# USB-NSTr_v3.net
KiCad netlist of a schematic drawn in Altium Designer
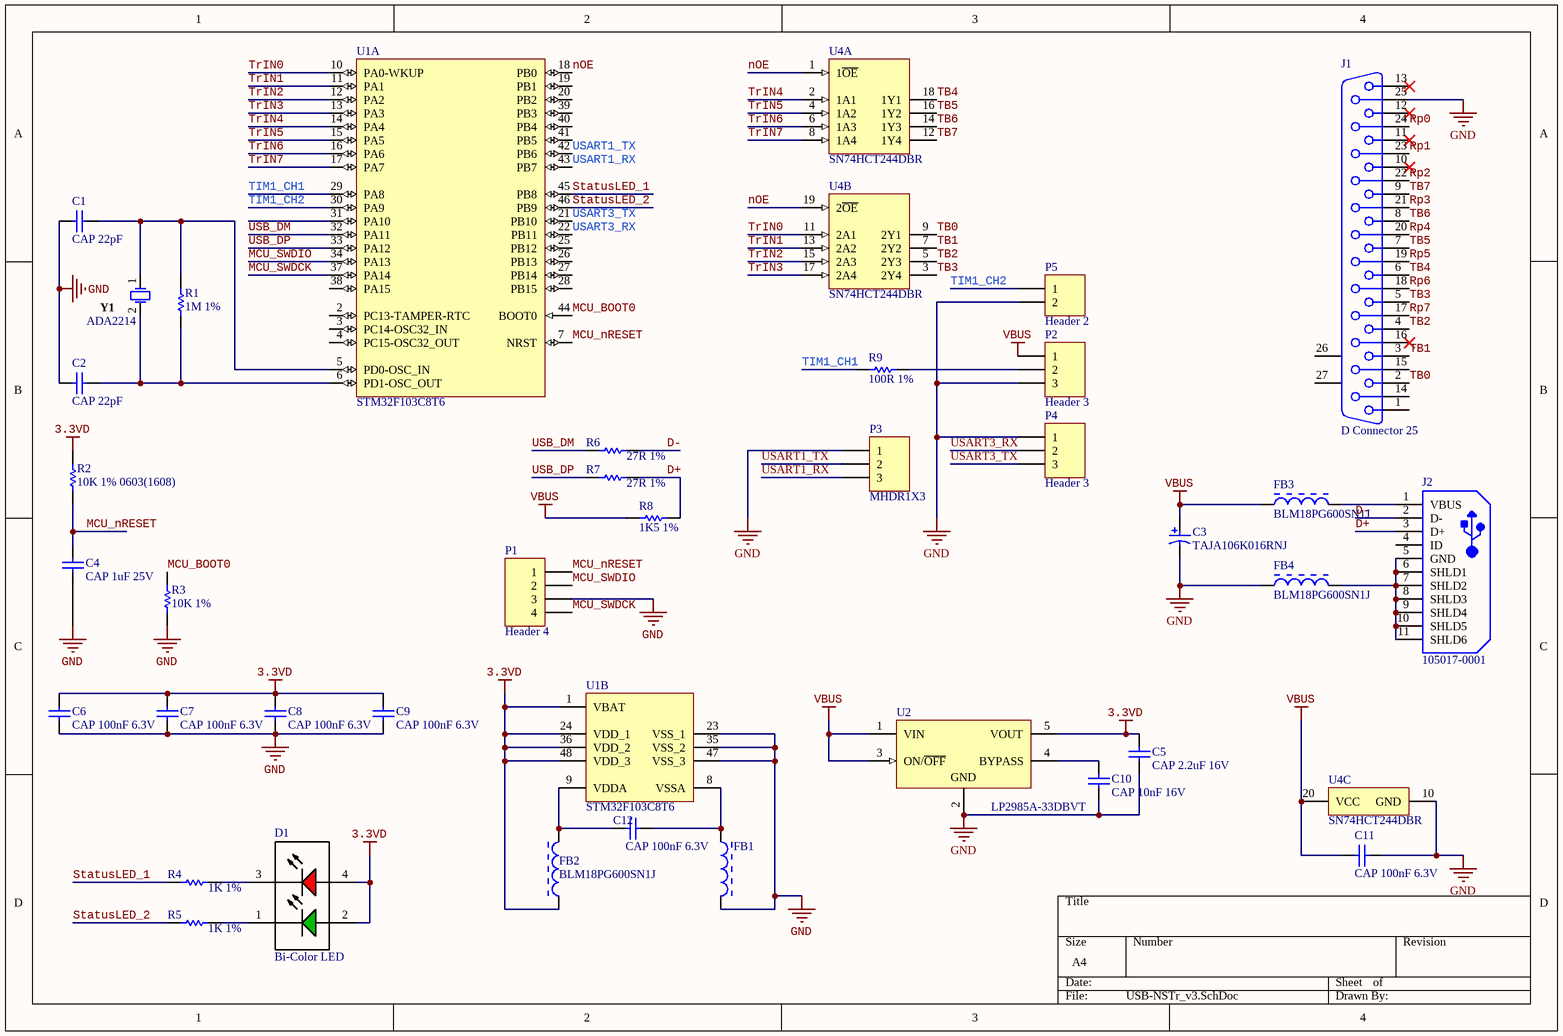
[diagram p0: USB-NSTr_v3.SchDoc]

(export (version "E")
  (design (tool "Eeschema 10.0.6"))
  (components
    (comp (ref "C1")
      (value "CAP 22pF")
      (footprint "CAPC0603(1608)100_N")
      (description "CAP 22pF 16V ±10% 0603 (1608 Metric) Thickness 1mm SMD")
      (fields (field (name "TOLERANCE") "Â±10%"))
      (libsource (lib "Altium Content Vault") (part "CAP"))
    )
    (comp (ref "C2")
      (value "CAP 22pF")
      (footprint "CAPC0603(1608)100_N")
      (description "CAP 22pF 16V ±10% 0603 (1608 Metric) Thickness 1mm SMD")
      (fields (field (name "TOLERANCE") "Â±10%"))
      (libsource (lib "Altium Content Vault") (part "CAP"))
    )
    (comp (ref "C3")
      (value "TAJA106K016RNJ")
      (footprint "CAPMP3217X18-T_V")
      (description "Standard Tantalum, 10 uF, +/- 10%, 16 V, -55 to 125 degC, 2-Pin SMD (1206), RoHS, Tape and Reel")
      (libsource (lib "Altium Content Vault") (part "CAP-P-2"))
    )
    (comp (ref "C4")
      (value "CAP 1uF 25V")
      (footprint "CAPC0603(1608)100_N")
      (description "CAP 1uF 25V ±20% 0603 (1608 Metric) Thickness 1mm SMD")
      (fields (field (name "TOLERANCE") "Â±20%"))
      (libsource (lib "Altium Content Vault") (part "CAP"))
    )
    (comp (ref "C5")
      (value "CAP 2.2uF 16V")
      (footprint "CAPC0603(1608)55_N")
      (description "CAP 2.2uF 16V ±20% 0603 (1608 Metric) Thickness 0.55mm SMD")
      (fields (field (name "TOLERANCE") "Â±20%"))
      (libsource (lib "Altium Content Vault") (part "CAP"))
    )
    (comp (ref "C6")
      (value "CAP 100nF 6.3V")
      (footprint "CAPC0603(1608)100_N")
      (description "CAP 100nF 6.3V ±10% 0603 (1608 Metric) Thickness 1mm SMD")
      (fields (field (name "TOLERANCE") "Â±10%"))
      (libsource (lib "Altium Content Vault") (part "CAP"))
    )
    (comp (ref "C7")
      (value "CAP 100nF 6.3V")
      (footprint "CAPC0603(1608)100_N")
      (description "CAP 100nF 6.3V ±10% 0603 (1608 Metric) Thickness 1mm SMD")
      (fields (field (name "TOLERANCE") "Â±10%"))
      (libsource (lib "Altium Content Vault") (part "CAP"))
    )
    (comp (ref "C8")
      (value "CAP 100nF 6.3V")
      (footprint "CAPC0603(1608)100_N")
      (description "CAP 100nF 6.3V ±10% 0603 (1608 Metric) Thickness 1mm SMD")
      (fields (field (name "TOLERANCE") "Â±10%"))
      (libsource (lib "Altium Content Vault") (part "CAP"))
    )
    (comp (ref "C9")
      (value "CAP 100nF 6.3V")
      (footprint "CAPC0603(1608)100_N")
      (description "CAP 100nF 6.3V ±10% 0603 (1608 Metric) Thickness 1mm SMD")
      (fields (field (name "TOLERANCE") "Â±10%"))
      (libsource (lib "Altium Content Vault") (part "CAP"))
    )
    (comp (ref "C10")
      (value "CAP 10nF 16V")
      (footprint "CAPC0603(1608)100_N")
      (description "CAP 10nF 16V ±5% 0603 (1608 Metric) Thickness 1mm SMD")
      (fields (field (name "TOLERANCE") "Â±5%"))
      (libsource (lib "Altium Content Vault") (part "CAP"))
    )
    (comp (ref "C11")
      (value "CAP 100nF 6.3V")
      (footprint "CAPC0603(1608)100_N")
      (description "CAP 100nF 6.3V ±10% 0603 (1608 Metric) Thickness 1mm SMD")
      (fields (field (name "TOLERANCE") "Â±10%"))
      (libsource (lib "Altium Content Vault") (part "CAP"))
    )
    (comp (ref "C12")
      (value "CAP 100nF 6.3V")
      (footprint "CAPC0603(1608)100_N")
      (description "CAP 100nF 6.3V ±10% 0603 (1608 Metric) Thickness 1mm SMD")
      (fields (field (name "TOLERANCE") "Â±10%"))
      (libsource (lib "Altium Content Vault") (part "CAP"))
    )
    (comp (ref "D1")
      (value "Bi-Color LED")
      (footprint "LED_Bi_Color_1204")
      (description "LED Indicator, Red / Green, 2 V, -40 to 100 degC, 4-Pin SMD, RoHS, Tape and Reel")
      (fields (field (name "MANUFACTURER") "Dialight"))
      (libsource (lib "MDR-36") (part "LED-RG-KAAK-4"))
    )
    (comp (ref "FB1")
      (value "BLM18PG600SN1J")
      (footprint "MURA-BLM18PG_KG-CHIP-2_V2")
      (fields (field (name "MANUFACTURER") "Murata"))
      (libsource (lib "Altium Content Vault") (part "MURA-FB-2"))
    )
    (comp (ref "FB2")
      (value "BLM18PG600SN1J")
      (footprint "MURA-BLM18PG_KG-CHIP-2_V2")
      (fields (field (name "MANUFACTURER") "Murata"))
      (libsource (lib "Altium Content Vault") (part "MURA-FB-2"))
    )
    (comp (ref "FB3")
      (value "BLM18PG600SN1J")
      (footprint "MURA-BLM18PG_KG-CHIP-2_V2")
      (fields (field (name "MANUFACTURER") "Murata"))
      (libsource (lib "Altium Content Vault") (part "MURA-FB-2"))
    )
    (comp (ref "FB4")
      (value "BLM18PG600SN1J")
      (footprint "MURA-BLM18PG_KG-CHIP-2_V2")
      (fields (field (name "MANUFACTURER") "Murata"))
      (libsource (lib "Altium Content Vault") (part "MURA-FB-2"))
    )
    (comp (ref "J1")
      (value "D Connector 25")
      (footprint "DB25-EDGE-Female-S")
      (description "Receptacle Assembly, 25 Position, Right Angle")
      (fields (field (name "PUBLISHER") "Altium Limited"))
      (libsource (lib "Miscellaneous Connectors") (part "D Connector 25"))
    )
    (comp (ref "J2")
      (value "105017-0001")
      (footprint "USB-MICRO-B_V")
      (fields (field (name "MANUFACTURER") "Molex"))
      (libsource (lib "Altium Content Vault") (part "USB-5-6SHLD"))
    )
    (comp (ref "P1")
      (value "Header 4")
      (footprint "PH2.0-LI-4P")
      (description "Header, 4-Pin")
      (fields (field (name "PUBLISHER") "Altium Limited"))
      (libsource (lib "Miscellaneous Connectors") (part "Header 4"))
    )
    (comp (ref "P2")
      (value "Header 3")
      (footprint "HDR1X3")
      (description "Header, 3-Pin")
      (fields (field (name "PUBLISHER") "Altium Limited"))
      (libsource (lib "Miscellaneous Connectors") (part "Header 3"))
    )
    (comp (ref "P3")
      (value "MHDR1X3")
      (footprint "HDR1X3")
      (description "Header, 3-Pin")
      (fields (field (name "PUBLISHER") "Altium Limited"))
      (libsource (lib "Miscellaneous Connectors") (part "MHDR1X3"))
    )
    (comp (ref "P4")
      (value "Header 3")
      (footprint "HDR1X3")
      (description "Header, 3-Pin")
      (fields (field (name "PUBLISHER") "Altium Limited"))
      (libsource (lib "Miscellaneous Connectors") (part "Header 3"))
    )
    (comp (ref "P5")
      (value "Header 2")
      (footprint "HDR1X2")
      (description "Header, 2-Pin")
      (fields (field (name "PUBLISHER") "Altium Limited"))
      (libsource (lib "Miscellaneous Connectors") (part "Header 2"))
    )
    (comp (ref "R1")
      (value "1M 1%")
      (footprint "RESC0603(1608)_N")
      (description "1M 0.1W 1% 0603 (1608 Metric)  SMD")
      (fields (field (name "POWER") "0.1 W") (field (name "TOLERANCE") "1 %"))
      (libsource (lib "Altium Content Vault") (part "RES"))
    )
    (comp (ref "R2")
      (value "10K 1% 0603(1608)")
      (footprint "RESC0603(1608)_N")
      (description "10K 0.1W 1% 0603 (1608 Metric)  SMD")
      (fields (field (name "POWER") "0.1 W") (field (name "TOLERANCE") "1 %"))
      (libsource (lib "Altium Content Vault") (part "RES"))
    )
    (comp (ref "R3")
      (value "10K 1%")
      (footprint "RESC0603(1608)_N")
      (description "10K 0.1W 1% 0603 (1608 Metric)  SMD")
      (fields (field (name "POWER") "0.1 W") (field (name "TOLERANCE") "1 %"))
      (libsource (lib "Altium Content Vault") (part "RES"))
    )
    (comp (ref "R4")
      (value "1K 1%")
      (footprint "RESC0603(1608)_N")
      (description "1K 0.1W 1% 0603 (1608 Metric)  SMD")
      (fields (field (name "TOLERANCE") "1 %") (field (name "POWER") "0.1 W"))
      (libsource (lib "Altium Content Vault") (part "RES"))
    )
    (comp (ref "R5")
      (value "1K 1%")
      (footprint "RESC0603(1608)_N")
      (description "1K 0.1W 1% 0603 (1608 Metric)  SMD")
      (fields (field (name "TOLERANCE") "1 %") (field (name "POWER") "0.1 W"))
      (libsource (lib "Altium Content Vault") (part "RES"))
    )
    (comp (ref "R6")
      (value "27R 1%")
      (footprint "RESC0603(1608)_N")
      (description "27R 0.1W 1% 0603 (1608 Metric)  SMD")
      (fields (field (name "TOLERANCE") "1 %") (field (name "POWER") "0.1 W"))
      (libsource (lib "Altium Content Vault") (part "RES"))
    )
    (comp (ref "R7")
      (value "27R 1%")
      (footprint "RESC0603(1608)_N")
      (description "27R 0.1W 1% 0603 (1608 Metric)  SMD")
      (fields (field (name "TOLERANCE") "1 %") (field (name "POWER") "0.1 W"))
      (libsource (lib "Altium Content Vault") (part "RES"))
    )
    (comp (ref "R8")
      (value "1K5 1%")
      (footprint "RESC0805(2012)_N")
      (description "1K5 0.125W 1% 0805 (2012 Metric)  SMD")
      (fields (field (name "POWER") "0.125 W") (field (name "TOLERANCE") "1 %"))
      (libsource (lib "Altium Content Vault") (part "RES"))
    )
    (comp (ref "R9")
      (value "100R 1%")
      (footprint "RESC0603(1608)_N")
      (description "100R 0.1W 1% 0603 (1608 Metric)  SMD")
      (fields (field (name "TOLERANCE") "1 %") (field (name "POWER") "0.1 W"))
      (libsource (lib "Altium Content Vault") (part "RES"))
    )
    (comp (ref "U1")
      (value "STM32F103C8T6")
      (footprint "STM-LQFP48_N")
      (libsource (lib "Altium Content Vault") (part "MC-ARM-STM32F103X8_B-SQ48"))
    )
    (comp (ref "U2")
      (value "LP2985A-33DBVT")
      (footprint "DBV0005A_N")
      (fields (field (name "MANUFACTURER") "Texas Instruments"))
      (libsource (lib "Altium Content Vault") (part "TI-LP2985_A-10DBV5"))
    )
    (comp (ref "U4")
      (value "SN74HCT244DBR")
      (footprint "DB0020A_N")
      (description "Octal Buffers And Line Drivers With 3-State Outputs, DB0020A, LARGE T&R")
      (fields
        (field (name "MANUFACTURER") "Texas Instruments")
        (field (name "GENERIC PART NUMBER") "SN74HCT244")
      )
      (libsource (lib "Altium Content Vault") (part "TI-SN54_74-XX020A-20"))
    )
    (comp (ref "Y1")
      (value "ADA2214")
      (footprint "ADAI-THHF-49S3")
      (description "Crystal, 12 MHz, 18 pF, 30 PPM, -20 to 70 degC, 2-Pin THD, RoHS")
      (libsource (lib "Altium Content Vault") (part "XTAL-1-2-2"))
    )
  )
  (nets
    (net (code "1") (name "/D+") (class "Default")
      (node (ref "J2") (pin "3") (pinfunction "D+_3") (pintype "passive"))
      (node (ref "R7") (pin "2") (pinfunction "2_2") (pintype "passive"))
      (node (ref "R8") (pin "1") (pinfunction "1_1") (pintype "passive"))
    )
    (net (code "2") (name "/D-") (class "Default")
      (node (ref "J2") (pin "2") (pinfunction "D-_2") (pintype "passive"))
      (node (ref "R6") (pin "2") (pinfunction "2_2") (pintype "passive"))
    )
    (net (code "3") (name "/MCU_BOOT0") (class "Default")
      (node (ref "R3") (pin "2") (pinfunction "2_2") (pintype "passive"))
      (node (ref "U1") (pin "44") (pinfunction "BOOT0_44") (pintype "input"))
    )
    (net (code "4") (name "/MCU_SWDCK") (class "Default")
      (node (ref "P1") (pin "4") (pinfunction "4_4") (pintype "passive"))
      (node (ref "U1") (pin "37") (pinfunction "PA14_37") (pintype "bidirectional"))
    )
    (net (code "5") (name "/MCU_SWDIO") (class "Default")
      (node (ref "P1") (pin "2") (pinfunction "2_2") (pintype "passive"))
      (node (ref "U1") (pin "34") (pinfunction "PA13_34") (pintype "bidirectional"))
    )
    (net (code "6") (name "/MCU_nRESET") (class "Default")
      (node (ref "C4") (pin "2") (pinfunction "2_2") (pintype "passive"))
      (node (ref "P1") (pin "1") (pinfunction "1_1") (pintype "passive"))
      (node (ref "R2") (pin "1") (pinfunction "1_1") (pintype "passive"))
      (node (ref "U1") (pin "7") (pinfunction "NRST_7") (pintype "bidirectional"))
    )
    (net (code "7") (name "/Rp0") (class "Default")
      (node (ref "J1") (pin "24") (pinfunction "24_24") (pintype "passive"))
    )
    (net (code "8") (name "/Rp1") (class "Default")
      (node (ref "J1") (pin "23") (pinfunction "23_23") (pintype "passive"))
    )
    (net (code "9") (name "/Rp2") (class "Default")
      (node (ref "J1") (pin "22") (pinfunction "22_22") (pintype "passive"))
    )
    (net (code "10") (name "/Rp3") (class "Default")
      (node (ref "J1") (pin "21") (pinfunction "21_21") (pintype "passive"))
    )
    (net (code "11") (name "/Rp4") (class "Default")
      (node (ref "J1") (pin "20") (pinfunction "20_20") (pintype "passive"))
    )
    (net (code "12") (name "/Rp5") (class "Default")
      (node (ref "J1") (pin "19") (pinfunction "19_19") (pintype "passive"))
    )
    (net (code "13") (name "/Rp6") (class "Default")
      (node (ref "J1") (pin "18") (pinfunction "18_18") (pintype "passive"))
    )
    (net (code "14") (name "/Rp7") (class "Default")
      (node (ref "J1") (pin "17") (pinfunction "17_17") (pintype "passive"))
    )
    (net (code "15") (name "/StatusLED_1") (class "Default")
      (node (ref "R4") (pin "1") (pinfunction "1_1") (pintype "passive"))
      (node (ref "U1") (pin "45") (pinfunction "PB8_45") (pintype "bidirectional"))
    )
    (net (code "16") (name "/StatusLED_2") (class "Default")
      (node (ref "R5") (pin "1") (pinfunction "1_1") (pintype "passive"))
      (node (ref "U1") (pin "46") (pinfunction "PB9_46") (pintype "bidirectional"))
    )
    (net (code "17") (name "/TB0") (class "Default")
      (node (ref "J1") (pin "2") (pinfunction "2_2") (pintype "passive"))
      (node (ref "U4") (pin "9") (pinfunction "2Y1_9") (pintype "tri_state"))
    )
    (net (code "18") (name "/TB1") (class "Default")
      (node (ref "J1") (pin "3") (pinfunction "3_3") (pintype "passive"))
      (node (ref "U4") (pin "7") (pinfunction "2Y2_7") (pintype "tri_state"))
    )
    (net (code "19") (name "/TB2") (class "Default")
      (node (ref "J1") (pin "4") (pinfunction "4_4") (pintype "passive"))
      (node (ref "U4") (pin "5") (pinfunction "2Y3_5") (pintype "tri_state"))
    )
    (net (code "20") (name "/TB3") (class "Default")
      (node (ref "J1") (pin "5") (pinfunction "5_5") (pintype "passive"))
      (node (ref "U4") (pin "3") (pinfunction "2Y4_3") (pintype "tri_state"))
    )
    (net (code "21") (name "/TB4") (class "Default")
      (node (ref "J1") (pin "6") (pinfunction "6_6") (pintype "passive"))
      (node (ref "U4") (pin "18") (pinfunction "1Y1_18") (pintype "tri_state"))
    )
    (net (code "22") (name "/TB5") (class "Default")
      (node (ref "J1") (pin "7") (pinfunction "7_7") (pintype "passive"))
      (node (ref "U4") (pin "16") (pinfunction "1Y2_16") (pintype "tri_state"))
    )
    (net (code "23") (name "/TB6") (class "Default")
      (node (ref "J1") (pin "8") (pinfunction "8_8") (pintype "passive"))
      (node (ref "U4") (pin "14") (pinfunction "1Y3_14") (pintype "tri_state"))
    )
    (net (code "24") (name "/TB7") (class "Default")
      (node (ref "J1") (pin "9") (pinfunction "9_9") (pintype "passive"))
      (node (ref "U4") (pin "12") (pinfunction "1Y4_12") (pintype "tri_state"))
    )
    (net (code "25") (name "/TIM1_CH1") (class "Default")
      (node (ref "R9") (pin "1") (pinfunction "1_1") (pintype "passive"))
      (node (ref "U1") (pin "29") (pinfunction "PA8_29") (pintype "bidirectional"))
    )
    (net (code "26") (name "/TIM1_CH2") (class "Default")
      (node (ref "P5") (pin "1") (pinfunction "1_1") (pintype "passive"))
      (node (ref "U1") (pin "30") (pinfunction "PA9_30") (pintype "bidirectional"))
    )
    (net (code "27") (name "/TrIN0") (class "Default")
      (node (ref "U1") (pin "10") (pinfunction "PA0-WKUP_10") (pintype "bidirectional"))
      (node (ref "U4") (pin "11") (pinfunction "2A1_11") (pintype "input"))
    )
    (net (code "28") (name "/TrIN1") (class "Default")
      (node (ref "U1") (pin "11") (pinfunction "PA1_11") (pintype "bidirectional"))
      (node (ref "U4") (pin "13") (pinfunction "2A2_13") (pintype "input"))
    )
    (net (code "29") (name "/TrIN2") (class "Default")
      (node (ref "U1") (pin "12") (pinfunction "PA2_12") (pintype "bidirectional"))
      (node (ref "U4") (pin "15") (pinfunction "2A3_15") (pintype "input"))
    )
    (net (code "30") (name "/TrIN3") (class "Default")
      (node (ref "U1") (pin "13") (pinfunction "PA3_13") (pintype "bidirectional"))
      (node (ref "U4") (pin "17") (pinfunction "2A4_17") (pintype "input"))
    )
    (net (code "31") (name "/TrIN4") (class "Default")
      (node (ref "U1") (pin "14") (pinfunction "PA4_14") (pintype "bidirectional"))
      (node (ref "U4") (pin "2") (pinfunction "1A1_2") (pintype "input"))
    )
    (net (code "32") (name "/TrIN5") (class "Default")
      (node (ref "U1") (pin "15") (pinfunction "PA5_15") (pintype "bidirectional"))
      (node (ref "U4") (pin "4") (pinfunction "1A2_4") (pintype "input"))
    )
    (net (code "33") (name "/TrIN6") (class "Default")
      (node (ref "U1") (pin "16") (pinfunction "PA6_16") (pintype "bidirectional"))
      (node (ref "U4") (pin "6") (pinfunction "1A3_6") (pintype "input"))
    )
    (net (code "34") (name "/TrIN7") (class "Default")
      (node (ref "U1") (pin "17") (pinfunction "PA7_17") (pintype "bidirectional"))
      (node (ref "U4") (pin "8") (pinfunction "1A4_8") (pintype "input"))
    )
    (net (code "35") (name "/USART1_RX") (class "Default")
      (node (ref "P3") (pin "3") (pinfunction "3_3") (pintype "passive"))
      (node (ref "U1") (pin "43") (pinfunction "PB7_43") (pintype "bidirectional"))
    )
    (net (code "36") (name "/USART1_TX") (class "Default")
      (node (ref "P3") (pin "2") (pinfunction "2_2") (pintype "passive"))
      (node (ref "U1") (pin "42") (pinfunction "PB6_42") (pintype "bidirectional"))
    )
    (net (code "37") (name "/USART3_RX") (class "Default")
      (node (ref "P4") (pin "2") (pinfunction "2_2") (pintype "passive"))
      (node (ref "U1") (pin "22") (pinfunction "PB11_22") (pintype "bidirectional"))
    )
    (net (code "38") (name "/USART3_TX") (class "Default")
      (node (ref "P4") (pin "3") (pinfunction "3_3") (pintype "passive"))
      (node (ref "U1") (pin "21") (pinfunction "PB10_21") (pintype "bidirectional"))
    )
    (net (code "39") (name "/USB_DM") (class "Default")
      (node (ref "R6") (pin "1") (pinfunction "1_1") (pintype "passive"))
      (node (ref "U1") (pin "32") (pinfunction "PA11_32") (pintype "bidirectional"))
    )
    (net (code "40") (name "/USB_DP") (class "Default")
      (node (ref "R7") (pin "1") (pinfunction "1_1") (pintype "passive"))
      (node (ref "U1") (pin "33") (pinfunction "PA12_33") (pintype "bidirectional"))
    )
    (net (code "41") (name "/nOE") (class "Default")
      (node (ref "U1") (pin "18") (pinfunction "PB0_18") (pintype "bidirectional"))
      (node (ref "U4") (pin "1") (pinfunction "1~{OE}_1") (pintype "input"))
      (node (ref "U4") (pin "19") (pinfunction "2~{OE}_19") (pintype "input"))
    )
    (net (code "42") (name "3.3VD") (class "Default")
      (node (ref "C5") (pin "2") (pinfunction "2_2") (pintype "passive"))
      (node (ref "C6") (pin "2") (pinfunction "2_2") (pintype "passive"))
      (node (ref "C7") (pin "2") (pinfunction "2_2") (pintype "passive"))
      (node (ref "C8") (pin "2") (pinfunction "2_2") (pintype "passive"))
      (node (ref "C9") (pin "2") (pinfunction "2_2") (pintype "passive"))
      (node (ref "D1") (pin "2") (pinfunction "Green-A_2") (pintype "passive"))
      (node (ref "D1") (pin "4") (pinfunction "Red-A_4") (pintype "passive"))
      (node (ref "FB2") (pin "1") (pinfunction "1_1") (pintype "passive"))
      (node (ref "R2") (pin "2") (pinfunction "2_2") (pintype "passive"))
      (node (ref "U1") (pin "1") (pinfunction "VBAT_1") (pintype "power_in"))
      (node (ref "U1") (pin "24") (pinfunction "VDD_1_24") (pintype "power_in"))
      (node (ref "U1") (pin "36") (pinfunction "VDD_2_36") (pintype "power_in"))
      (node (ref "U1") (pin "48") (pinfunction "VDD_3_48") (pintype "power_in"))
      (node (ref "U2") (pin "5") (pinfunction "VOUT_5") (pintype "power_in"))
    )
    (net (code "43") (name "GND") (class "Default")
      (node (ref "C1") (pin "2") (pinfunction "2_2") (pintype "passive"))
      (node (ref "C10") (pin "1") (pinfunction "1_1") (pintype "passive"))
      (node (ref "C11") (pin "1") (pinfunction "1_1") (pintype "passive"))
      (node (ref "C2") (pin "2") (pinfunction "2_2") (pintype "passive"))
      (node (ref "C3") (pin "2") (pinfunction "2_2") (pintype "passive"))
      (node (ref "C4") (pin "1") (pinfunction "1_1") (pintype "passive"))
      (node (ref "C5") (pin "1") (pinfunction "1_1") (pintype "passive"))
      (node (ref "C6") (pin "1") (pinfunction "1_1") (pintype "passive"))
      (node (ref "C7") (pin "1") (pinfunction "1_1") (pintype "passive"))
      (node (ref "C8") (pin "1") (pinfunction "1_1") (pintype "passive"))
      (node (ref "C9") (pin "1") (pinfunction "1_1") (pintype "passive"))
      (node (ref "FB1") (pin "2") (pinfunction "2_2") (pintype "passive"))
      (node (ref "FB4") (pin "1") (pinfunction "1_1") (pintype "passive"))
      (node (ref "J1") (pin "25") (pinfunction "25_25") (pintype "passive"))
      (node (ref "P1") (pin "3") (pinfunction "3_3") (pintype "passive"))
      (node (ref "P2") (pin "3") (pinfunction "3_3") (pintype "passive"))
      (node (ref "P3") (pin "1") (pinfunction "1_1") (pintype "passive"))
      (node (ref "P4") (pin "1") (pinfunction "1_1") (pintype "passive"))
      (node (ref "P5") (pin "2") (pinfunction "2_2") (pintype "passive"))
      (node (ref "R3") (pin "1") (pinfunction "1_1") (pintype "passive"))
      (node (ref "U1") (pin "23") (pinfunction "VSS_1_23") (pintype "power_in"))
      (node (ref "U1") (pin "35") (pinfunction "VSS_2_35") (pintype "power_in"))
      (node (ref "U1") (pin "47") (pinfunction "VSS_3_47") (pintype "power_in"))
      (node (ref "U2") (pin "2") (pinfunction "GND_2") (pintype "power_in"))
      (node (ref "U4") (pin "10") (pinfunction "GND_10") (pintype "power_in"))
    )
    (net (code "44") (name "Net-(D1-Green-C)") (class "Default")
      (node (ref "D1") (pin "1") (pinfunction "Green-C_1") (pintype "passive"))
      (node (ref "R5") (pin "2") (pinfunction "2_2") (pintype "passive"))
    )
    (net (code "45") (name "Net-(D1-Red-C)") (class "Default")
      (node (ref "D1") (pin "3") (pinfunction "Red-C_3") (pintype "passive"))
      (node (ref "R4") (pin "2") (pinfunction "2_2") (pintype "passive"))
    )
    (net (code "46") (name "Net-(J2-GND)") (class "Default")
      (node (ref "FB4") (pin "2") (pinfunction "2_2") (pintype "passive"))
      (node (ref "J2") (pin "10") (pinfunction "SHLD5_10") (pintype "passive"))
      (node (ref "J2") (pin "11") (pinfunction "SHLD6_11") (pintype "passive"))
      (node (ref "J2") (pin "5") (pinfunction "GND_5") (pintype "passive"))
      (node (ref "J2") (pin "6") (pinfunction "SHLD1_6") (pintype "passive"))
      (node (ref "J2") (pin "7") (pinfunction "SHLD2_7") (pintype "passive"))
      (node (ref "J2") (pin "8") (pinfunction "SHLD3_8") (pintype "passive"))
      (node (ref "J2") (pin "9") (pinfunction "SHLD4_9") (pintype "passive"))
    )
    (net (code "47") (name "Net-(J2-VBUS)") (class "Default")
      (node (ref "FB3") (pin "2") (pinfunction "2_2") (pintype "passive"))
      (node (ref "J2") (pin "1") (pinfunction "VBUS_1") (pintype "passive"))
    )
    (net (code "48") (name "Net-(P2-Pad2)") (class "Default")
      (node (ref "P2") (pin "2") (pinfunction "2_2") (pintype "passive"))
      (node (ref "R9") (pin "2") (pinfunction "2_2") (pintype "passive"))
    )
    (net (code "49") (name "Net-(U1A-PD0-OSC_IN)") (class "Default")
      (node (ref "C1") (pin "1") (pinfunction "1_1") (pintype "passive"))
      (node (ref "R1") (pin "2") (pinfunction "2_2") (pintype "passive"))
      (node (ref "U1") (pin "5") (pinfunction "PD0-OSC_IN_5") (pintype "bidirectional"))
      (node (ref "Y1") (pin "1") (pinfunction "1_1") (pintype "passive"))
    )
    (net (code "50") (name "Net-(U1A-PD1-OSC_OUT)") (class "Default")
      (node (ref "C2") (pin "1") (pinfunction "1_1") (pintype "passive"))
      (node (ref "R1") (pin "1") (pinfunction "1_1") (pintype "passive"))
      (node (ref "U1") (pin "6") (pinfunction "PD1-OSC_OUT_6") (pintype "bidirectional"))
      (node (ref "Y1") (pin "2") (pinfunction "2_2") (pintype "passive"))
    )
    (net (code "51") (name "Net-(U1B-VDDA)") (class "Default")
      (node (ref "C12") (pin "2") (pinfunction "2_2") (pintype "passive"))
      (node (ref "FB2") (pin "2") (pinfunction "2_2") (pintype "passive"))
      (node (ref "U1") (pin "9") (pinfunction "VDDA_9") (pintype "power_in"))
    )
    (net (code "52") (name "Net-(U1B-VSSA)") (class "Default")
      (node (ref "C12") (pin "1") (pinfunction "1_1") (pintype "passive"))
      (node (ref "FB1") (pin "1") (pinfunction "1_1") (pintype "passive"))
      (node (ref "U1") (pin "8") (pinfunction "VSSA_8") (pintype "power_in"))
    )
    (net (code "53") (name "Net-(U2-BYPASS)") (class "Default")
      (node (ref "C10") (pin "2") (pinfunction "2_2") (pintype "passive"))
      (node (ref "U2") (pin "4") (pinfunction "BYPASS_4") (pintype "passive"))
    )
    (net (code "54") (name "VBUS") (class "Default")
      (node (ref "C11") (pin "2") (pinfunction "2_2") (pintype "passive"))
      (node (ref "C3") (pin "1") (pinfunction "1_1") (pintype "passive"))
      (node (ref "FB3") (pin "1") (pinfunction "1_1") (pintype "passive"))
      (node (ref "P2") (pin "1") (pinfunction "1_1") (pintype "passive"))
      (node (ref "R8") (pin "2") (pinfunction "2_2") (pintype "passive"))
      (node (ref "U2") (pin "1") (pinfunction "VIN_1") (pintype "power_in"))
      (node (ref "U2") (pin "3") (pinfunction "ON/~{OFF}_3") (pintype "input"))
      (node (ref "U4") (pin "20") (pinfunction "VCC_20") (pintype "power_in"))
    )
    (net (code "55") (name "unconnected-(J1-MH1-Pad26)") (class "Default")
      (node (ref "J1") (pin "26") (pinfunction "MH1_26") (pintype "passive"))
    )
    (net (code "56") (name "unconnected-(J1-MH2-Pad27)") (class "Default")
      (node (ref "J1") (pin "27") (pinfunction "MH2_27") (pintype "passive"))
    )
    (net (code "57") (name "unconnected-(J1-Pad1)") (class "Default")
      (node (ref "J1") (pin "1") (pinfunction "1_1") (pintype "passive"))
    )
    (net (code "58") (name "unconnected-(J1-Pad10)") (class "Default")
      (node (ref "J1") (pin "10") (pinfunction "10_10") (pintype "passive+no_connect"))
    )
    (net (code "59") (name "unconnected-(J1-Pad11)") (class "Default")
      (node (ref "J1") (pin "11") (pinfunction "11_11") (pintype "passive+no_connect"))
    )
    (net (code "60") (name "unconnected-(J1-Pad12)") (class "Default")
      (node (ref "J1") (pin "12") (pinfunction "12_12") (pintype "passive+no_connect"))
    )
    (net (code "61") (name "unconnected-(J1-Pad13)") (class "Default")
      (node (ref "J1") (pin "13") (pinfunction "13_13") (pintype "passive+no_connect"))
    )
    (net (code "62") (name "unconnected-(J1-Pad14)") (class "Default")
      (node (ref "J1") (pin "14") (pinfunction "14_14") (pintype "passive"))
    )
    (net (code "63") (name "unconnected-(J1-Pad15)") (class "Default")
      (node (ref "J1") (pin "15") (pinfunction "15_15") (pintype "passive"))
    )
    (net (code "64") (name "unconnected-(J1-Pad16)") (class "Default")
      (node (ref "J1") (pin "16") (pinfunction "16_16") (pintype "passive+no_connect"))
    )
    (net (code "65") (name "unconnected-(J2-ID-Pad4)") (class "Default")
      (node (ref "J2") (pin "4") (pinfunction "ID_4") (pintype "passive"))
    )
    (net (code "66") (name "unconnected-(U1A-PA10-Pad31)") (class "Default")
      (node (ref "U1") (pin "31") (pinfunction "PA10_31") (pintype "bidirectional"))
    )
    (net (code "67") (name "unconnected-(U1A-PA15-Pad38)") (class "Default")
      (node (ref "U1") (pin "38") (pinfunction "PA15_38") (pintype "bidirectional"))
    )
    (net (code "68") (name "unconnected-(U1A-PB1-Pad19)") (class "Default")
      (node (ref "U1") (pin "19") (pinfunction "PB1_19") (pintype "bidirectional"))
    )
    (net (code "69") (name "unconnected-(U1A-PB2-Pad20)") (class "Default")
      (node (ref "U1") (pin "20") (pinfunction "PB2_20") (pintype "bidirectional"))
    )
    (net (code "70") (name "unconnected-(U1A-PB3-Pad39)") (class "Default")
      (node (ref "U1") (pin "39") (pinfunction "PB3_39") (pintype "bidirectional"))
    )
    (net (code "71") (name "unconnected-(U1A-PB4-Pad40)") (class "Default")
      (node (ref "U1") (pin "40") (pinfunction "PB4_40") (pintype "bidirectional"))
    )
    (net (code "72") (name "unconnected-(U1A-PB5-Pad41)") (class "Default")
      (node (ref "U1") (pin "41") (pinfunction "PB5_41") (pintype "bidirectional"))
    )
    (net (code "73") (name "unconnected-(U1A-PB12-Pad25)") (class "Default")
      (node (ref "U1") (pin "25") (pinfunction "PB12_25") (pintype "bidirectional"))
    )
    (net (code "74") (name "unconnected-(U1A-PB13-Pad26)") (class "Default")
      (node (ref "U1") (pin "26") (pinfunction "PB13_26") (pintype "bidirectional"))
    )
    (net (code "75") (name "unconnected-(U1A-PB14-Pad27)") (class "Default")
      (node (ref "U1") (pin "27") (pinfunction "PB14_27") (pintype "bidirectional"))
    )
    (net (code "76") (name "unconnected-(U1A-PB15-Pad28)") (class "Default")
      (node (ref "U1") (pin "28") (pinfunction "PB15_28") (pintype "bidirectional"))
    )
    (net (code "77") (name "unconnected-(U1A-PC13-TAMPER-RTC-Pad2)") (class "Default")
      (node (ref "U1") (pin "2") (pinfunction "PC13-TAMPER-RTC_2") (pintype "bidirectional"))
    )
    (net (code "78") (name "unconnected-(U1A-PC14-OSC32_IN-Pad3)") (class "Default")
      (node (ref "U1") (pin "3") (pinfunction "PC14-OSC32_IN_3") (pintype "bidirectional"))
    )
    (net (code "79") (name "unconnected-(U1A-PC15-OSC32_OUT-Pad4)") (class "Default")
      (node (ref "U1") (pin "4") (pinfunction "PC15-OSC32_OUT_4") (pintype "bidirectional"))
    )
  )
)
